# buckconverterhr.net
KiCad netlist of a schematic drawn in EAGLE
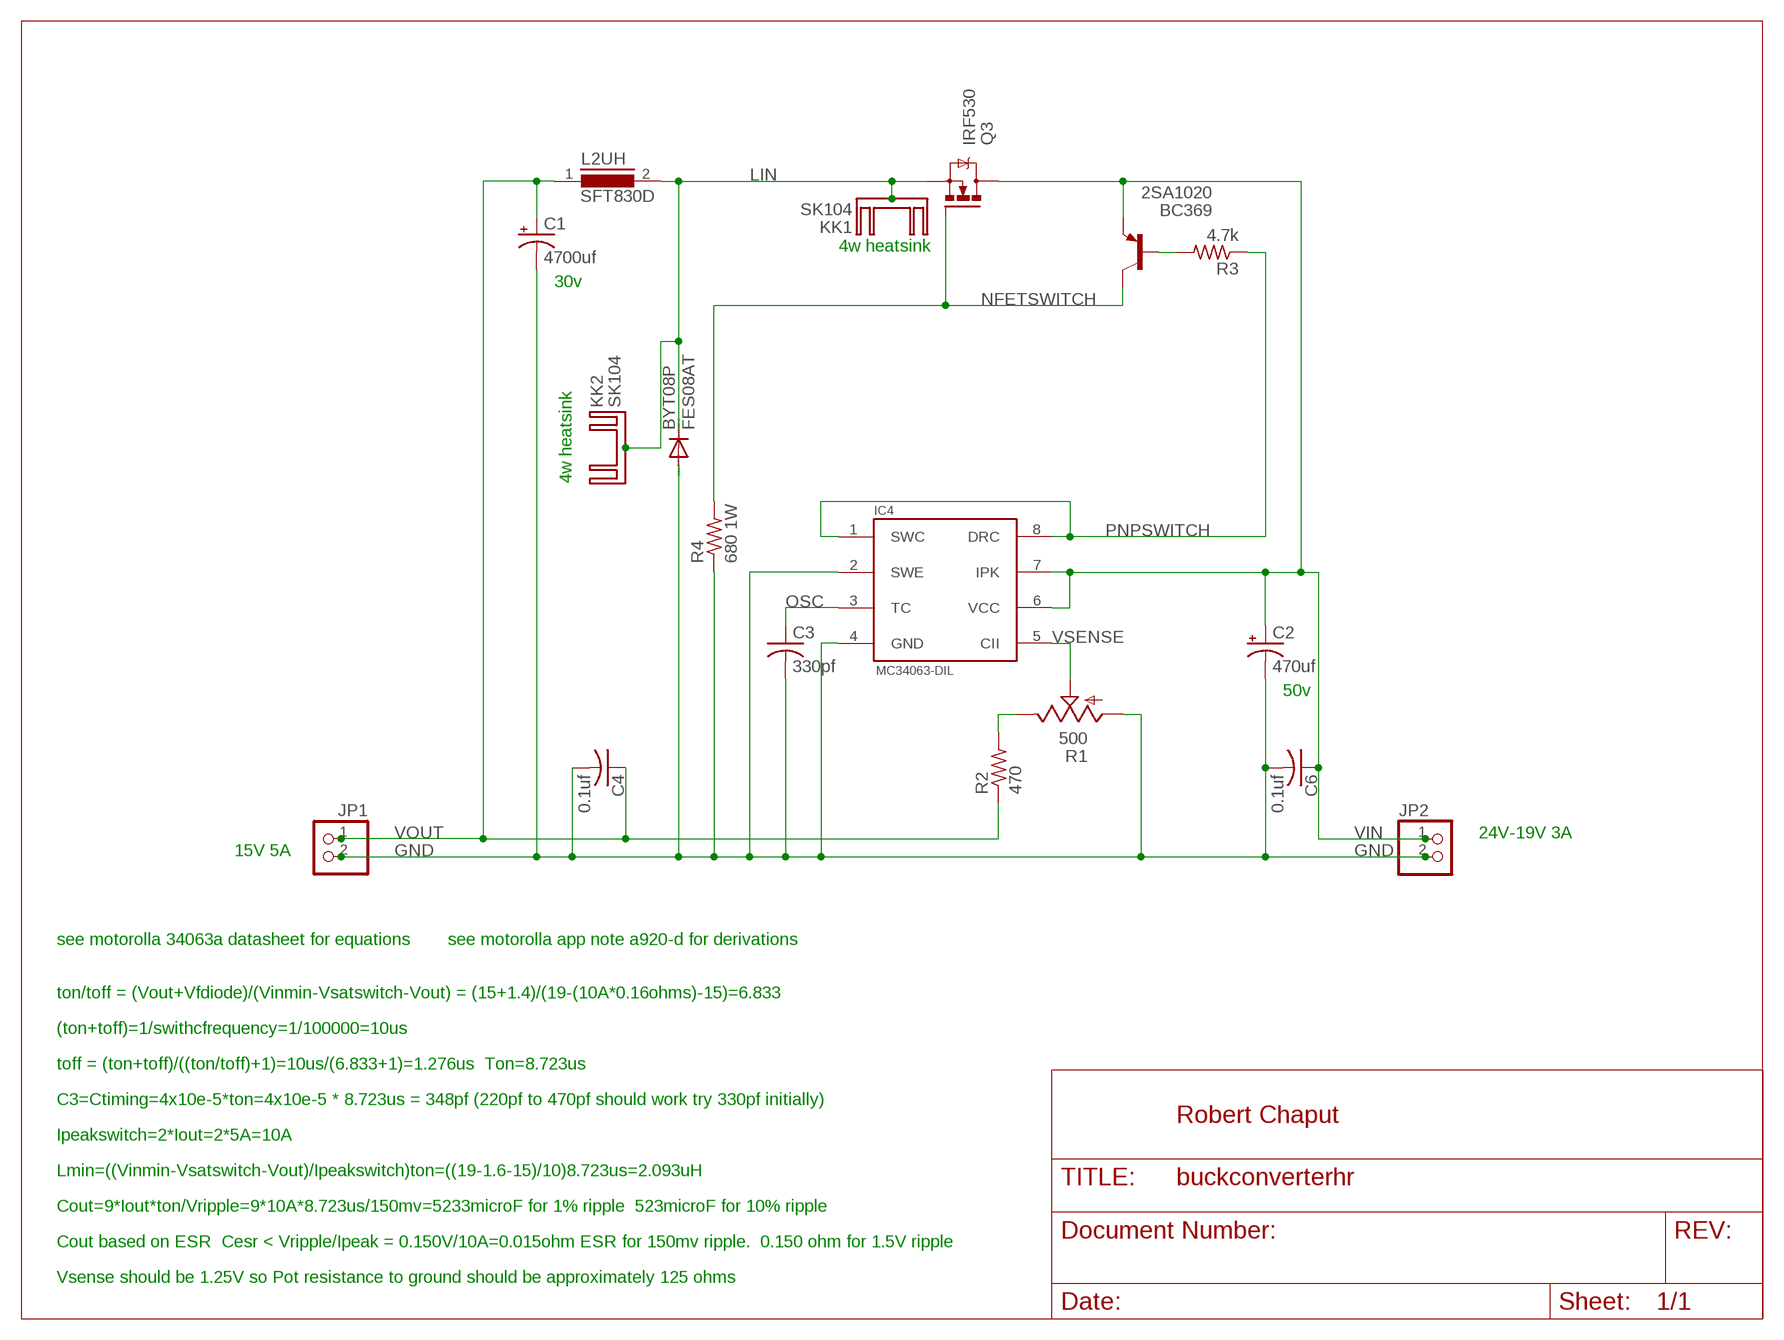
[diagram p0: schematic, sheet 1]

(export (version "E")
  (design (tool "Eeschema 10.0.6"))
  (components
    (comp (ref "2SA1020")
      (value "BC369")
      (footprint "eagle-import:TO92-BCE")
      (libsource (lib "eagle-import") (part "BC369"))
    )
    (comp (ref "BYT08P")
      (value "FES08AT")
      (footprint "eagle-import:DO220S")
      (libsource (lib "eagle-import") (part "FES08AT"))
    )
    (comp (ref "C1")
      (value "4700uf")
      (footprint "eagle-import:EB30D")
      (libsource (lib "eagle-import") (part "CPOL-USE10-30"))
    )
    (comp (ref "C2")
      (value "470uf")
      (footprint "eagle-import:E5-8,5")
      (libsource (lib "eagle-import") (part "CPOL-USE5-8.5"))
    )
    (comp (ref "C3")
      (value "330pf")
      (footprint "eagle-import:C050-030X075")
      (libsource (lib "eagle-import") (part "C-US050-030X075"))
    )
    (comp (ref "C4")
      (value "0.1uf")
      (footprint "eagle-import:C050-030X075")
      (libsource (lib "eagle-import") (part "C-US050-030X075"))
    )
    (comp (ref "C6")
      (value "0.1uf")
      (footprint "eagle-import:C050-030X075")
      (libsource (lib "eagle-import") (part "C-US050-030X075"))
    )
    (comp (ref "IC4")
      (value "MC34063-DIL")
      (footprint "eagle-import:DIL08")
      (libsource (lib "eagle-import") (part "MC34063-DIL"))
    )
    (comp (ref "JP1")
      (value "PINHD-1X2")
      (footprint "eagle-import:1X02")
      (libsource (lib "eagle-import") (part "PINHD-1X2"))
    )
    (comp (ref "JP2")
      (value "PINHD-1X2")
      (footprint "eagle-import:1X02")
      (libsource (lib "eagle-import") (part "PINHD-1X2"))
    )
    (comp (ref "KK1")
      (value "SK104")
      (footprint "eagle-import:SK104")
      (libsource (lib "eagle-import") (part "SK104"))
    )
    (comp (ref "KK2")
      (value "SK104")
      (footprint "eagle-import:SK104")
      (libsource (lib "eagle-import") (part "SK104"))
    )
    (comp (ref "L2UH")
      (value "SFT830D")
      (footprint "eagle-import:SFT830D")
      (libsource (lib "eagle-import") (part "SFT830D"))
    )
    (comp (ref "Q3")
      (value "IRF530")
      (footprint "eagle-import:TO220BV")
      (libsource (lib "eagle-import") (part "IRF530"))
    )
    (comp (ref "R1")
      (value "500")
      (footprint "eagle-import:PT-SPIN")
      (libsource (lib "eagle-import") (part "TRIM_US-PTSPIN"))
    )
    (comp (ref "R2")
      (value "470")
      (footprint "eagle-import:0309V")
      (libsource (lib "eagle-import") (part "R-US_0309/V"))
    )
    (comp (ref "R3")
      (value "4.7k")
      (footprint "eagle-import:0309V")
      (libsource (lib "eagle-import") (part "R-US_0309/V"))
    )
    (comp (ref "R4")
      (value "680 1W")
      (footprint "eagle-import:P0613V")
      (libsource (lib "eagle-import") (part "R-US_0613/5V"))
    )
  )
  (nets
    (net (code "1") (name "/GND") (class "Default")
      (node (ref "BYT08P") (pin "A") (pinfunction "A_A") (pintype "passive"))
      (node (ref "C1") (pin "-") (pinfunction "-_-") (pintype "passive"))
      (node (ref "C2") (pin "-") (pinfunction "-_-") (pintype "passive"))
      (node (ref "C3") (pin "2") (pinfunction "2_2") (pintype "passive"))
      (node (ref "C4") (pin "2") (pinfunction "2_2") (pintype "passive"))
      (node (ref "C6") (pin "2") (pinfunction "2_2") (pintype "passive"))
      (node (ref "IC4") (pin "2") (pinfunction "SWE_2") (pintype "bidirectional"))
      (node (ref "IC4") (pin "4") (pinfunction "GND_4") (pintype "power_in"))
      (node (ref "JP1") (pin "2") (pinfunction "2_2") (pintype "passive"))
      (node (ref "JP2") (pin "2") (pinfunction "2_2") (pintype "passive"))
      (node (ref "R1") (pin "A") (pinfunction "A_A") (pintype "passive"))
      (node (ref "R4") (pin "1") (pinfunction "1_1") (pintype "passive"))
    )
    (net (code "2") (name "/LIN") (class "Default")
      (node (ref "BYT08P") (pin "C") (pinfunction "C_C") (pintype "passive"))
      (node (ref "L2UH") (pin "2") (pinfunction "2_2") (pintype "passive"))
      (node (ref "Q3") (pin "S") (pinfunction "S_S") (pintype "passive"))
    )
    (net (code "3") (name "/NFETSWITCH") (class "Default")
      (node (ref "2SA1020") (pin "C") (pinfunction "C_C") (pintype "passive"))
      (node (ref "Q3") (pin "G") (pinfunction "G_G") (pintype "passive"))
      (node (ref "R4") (pin "2") (pinfunction "2_2") (pintype "passive"))
    )
    (net (code "4") (name "/OSC") (class "Default")
      (node (ref "C3") (pin "1") (pinfunction "1_1") (pintype "passive"))
      (node (ref "IC4") (pin "3") (pinfunction "TC_3") (pintype "bidirectional"))
    )
    (net (code "5") (name "/PNPSWITCH") (class "Default")
      (node (ref "IC4") (pin "1") (pinfunction "SWC_1") (pintype "bidirectional"))
      (node (ref "IC4") (pin "8") (pinfunction "DRC_8") (pintype "bidirectional"))
      (node (ref "R3") (pin "1") (pinfunction "1_1") (pintype "passive"))
    )
    (net (code "6") (name "/VIN") (class "Default")
      (node (ref "2SA1020") (pin "E") (pinfunction "E_E") (pintype "passive"))
      (node (ref "C2") (pin "+") (pinfunction "+_+") (pintype "passive"))
      (node (ref "C6") (pin "1") (pinfunction "1_1") (pintype "passive"))
      (node (ref "IC4") (pin "6") (pinfunction "VCC_6") (pintype "bidirectional"))
      (node (ref "IC4") (pin "7") (pinfunction "IPK_7") (pintype "bidirectional"))
      (node (ref "JP2") (pin "1") (pinfunction "1_1") (pintype "passive"))
      (node (ref "Q3") (pin "D") (pinfunction "D_D") (pintype "passive"))
    )
    (net (code "7") (name "/VOUT") (class "Default")
      (node (ref "C1") (pin "+") (pinfunction "+_+") (pintype "passive"))
      (node (ref "C4") (pin "1") (pinfunction "1_1") (pintype "passive"))
      (node (ref "JP1") (pin "1") (pinfunction "1_1") (pintype "passive"))
      (node (ref "L2UH") (pin "1") (pinfunction "1_1") (pintype "passive"))
      (node (ref "R2") (pin "1") (pinfunction "1_1") (pintype "passive"))
    )
    (net (code "8") (name "/VSENSE") (class "Default")
      (node (ref "IC4") (pin "5") (pinfunction "CII_5") (pintype "bidirectional"))
      (node (ref "R1") (pin "S") (pinfunction "S_S") (pintype "passive"))
    )
    (net (code "9") (name "Net-(2SA1020-PadB)") (class "Default")
      (node (ref "2SA1020") (pin "B") (pinfunction "B_B") (pintype "passive"))
      (node (ref "R3") (pin "2") (pinfunction "2_2") (pintype "passive"))
    )
    (net (code "10") (name "Net-(R1-PadE)") (class "Default")
      (node (ref "R1") (pin "E") (pinfunction "E_E") (pintype "passive"))
      (node (ref "R2") (pin "2") (pinfunction "2_2") (pintype "passive"))
    )
  )
)
